# Zoul.net
KiCad netlist of a schematic drawn in Altium Designer
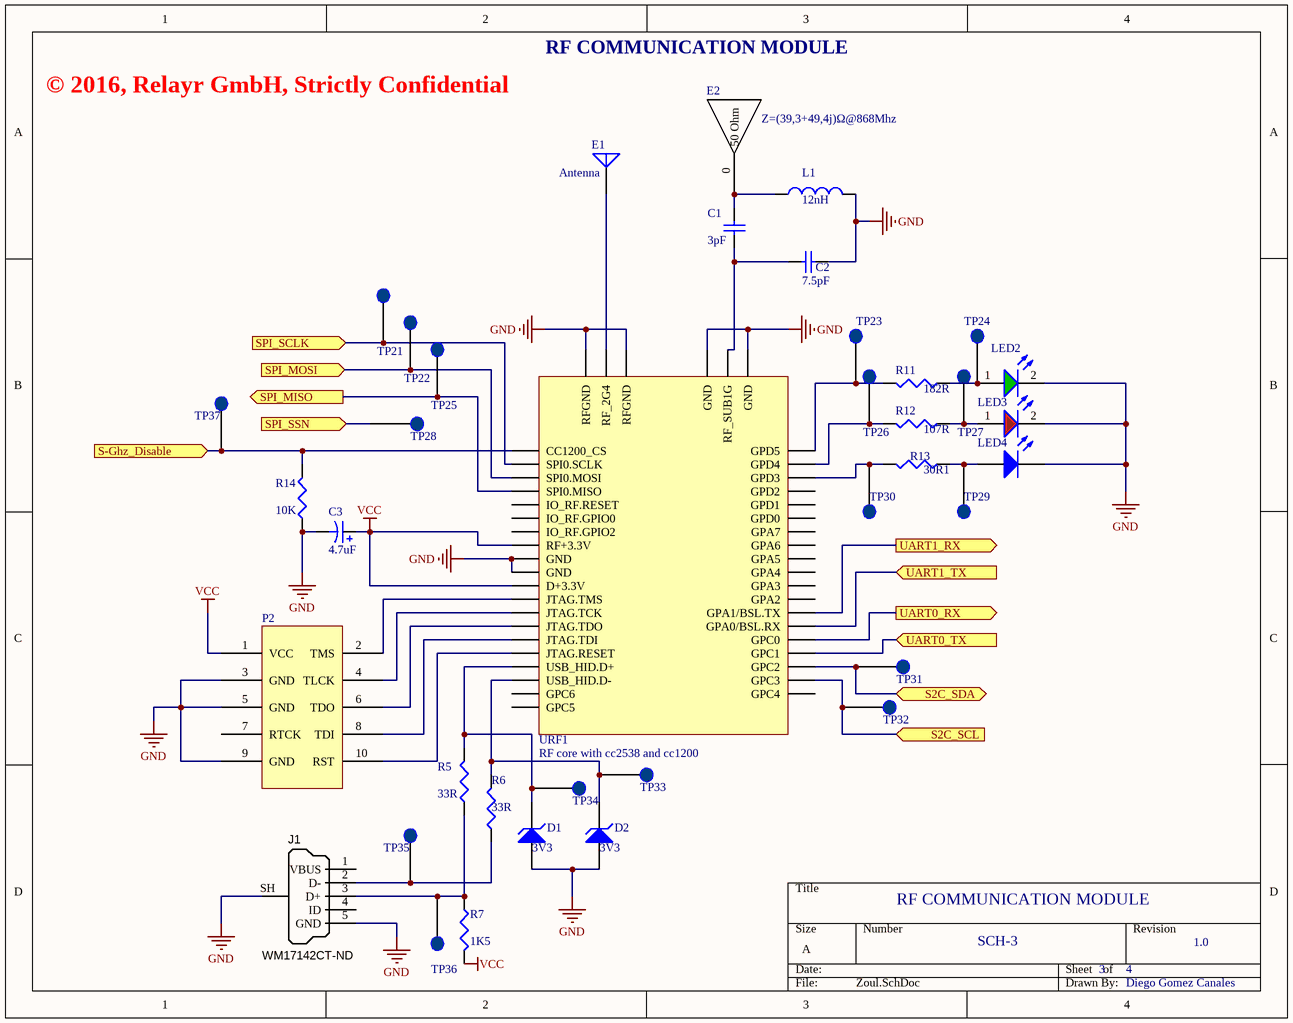
[diagram p0: Zoul.SchDoc]

(export (version "E")
  (design (tool "Eeschema 10.0.6"))
  (components
    (comp (ref "C1")
      (value "3pF")
      (footprint "6-0805_N")
      (description "Capacitor")
      (fields (field (name "Comment") "Cap") (field (name "PUBLISHER") "Altium Limited"))
      (libsource (lib "Miscellaneous Devices") (part "Cap"))
    )
    (comp (ref "C2")
      (value "7.5pF")
      (footprint "6-0805_N")
      (description "Capacitor")
      (fields (field (name "Comment") "Cap") (field (name "PUBLISHER") "Altium Limited"))
      (libsource (lib "Miscellaneous Devices") (part "Cap"))
    )
    (comp (ref "C3")
      (value "4.7uF")
      (footprint "C0805")
      (description "Polarized Capacitor (Surface Mount)")
      (fields (field (name "Comment") "Cap Pol3") (field (name "PUBLISHER") "Altium Limited"))
      (libsource (lib "Miscellaneous Devices") (part "Cap Pol3"))
    )
    (comp (ref "D1")
      (value "3V3")
      (footprint "425")
      (description "Zener Diode")
      (fields (field (name "PUBLISHER") "Altium Limited"))
      (libsource (lib "Miscellaneous Devices") (part "D Zener"))
    )
    (comp (ref "D2")
      (value "3V3")
      (footprint "425")
      (description "Zener Diode")
      (fields (field (name "PUBLISHER") "Altium Limited"))
      (libsource (lib "Miscellaneous Devices") (part "D Zener"))
    )
    (comp (ref "E1")
      (value "Antenna")
      (footprint "INDC3216")
      (description "Generic Antenna")
      (fields (field (name "PUBLISHER") "Altium Limited"))
      (libsource (lib "Miscellaneous Devices") (part "Antenna"))
    )
    (comp (ref "E2")
      (value "Component_1")
      (footprint "DNO24")
      (description "Antenna SubGhz PCB")
      (libsource (lib "SubGhz AntPCB") (part "Component_1"))
    )
    (comp (ref "J1")
      (value "USB Micro Type B")
      (footprint "USB_Micro-B_Molex_SMD")
      (description "Connector SMD USB Micro Type B middle mount")
      (fields (field (name "SUPPLIER PART NUMBER 1") "WM17142CT-ND"))
      (libsource (lib "Pasive_components") (part "USB_Micro_TypeB_1"))
    )
    (comp (ref "L1")
      (value "12nH")
      (footprint "6-0805_N")
      (description "Inductor")
      (fields (field (name "PUBLISHER") "Altium Limited"))
      (libsource (lib "Miscellaneous Devices") (part "Inductor"))
    )
    (comp (ref "LED2")
      (value "150080GS75000")
      (footprint "6-0805_N")
      (description "SMD mono-color Chip LED, WL-SMCW, Green")
      (fields
        (field (name "MANUFACTURER") "W黵th Elektronik eiSos GmbH")
        (field (name "CREATED BY") "Christin Otto")
      )
      (libsource (lib "SMD_LEDs") (part "WL-SMCW 0805  150080GS75000"))
    )
    (comp (ref "LED3")
      (value "150080RS75000")
      (footprint "6-0805_N")
      (description "SMD mono-color Chip LED, WL-SMCW, Red")
      (fields
        (field (name "MANUFACTURER") "W黵th Elektronik eiSos GmbH")
        (field (name "CREATED BY") "Christin Otto")
      )
      (libsource (lib "SMD_LEDs") (part "WL-SMCW 0805  150080RS75000"))
    )
    (comp (ref "LED4")
      (value "5988191107F")
      (footprint "6-0805_N")
      (description "Blue 473nm LED Indication - Discrete 3.2V 0805 (2012 Metric)")
      (fields (field (name "PUBLISHER") "Altium Limited"))
      (libsource (lib "Miscellaneous Devices") (part "LED0"))
    )
    (comp (ref "P2")
      (value "FTSH-105-01-L-DV-K")
      (footprint "JTAG")
      (libsource (lib "jtagConnector") (part "Component_1"))
    )
    (comp (ref "R5")
      (value "33R")
      (footprint "6-0805_N")
      (description "Resistor")
      (fields (field (name "Comment") "Res3") (field (name "PUBLISHER") "Altium Limited"))
      (libsource (lib "Miscellaneous Devices") (part "Res3"))
    )
    (comp (ref "R6")
      (value "33R")
      (footprint "6-0805_N")
      (description "Resistor")
      (fields (field (name "Comment") "Res3") (field (name "PUBLISHER") "Altium Limited"))
      (libsource (lib "Miscellaneous Devices") (part "Res3"))
    )
    (comp (ref "R7")
      (value "1K5")
      (footprint "6-0805_N")
      (description "Resistor")
      (fields (field (name "Comment") "Res3") (field (name "PUBLISHER") "Altium Limited"))
      (libsource (lib "Miscellaneous Devices") (part "Res3"))
    )
    (comp (ref "R11")
      (value "182R")
      (footprint "6-0805_N")
      (description "Resistor")
      (fields (field (name "Comment") "Res3") (field (name "PUBLISHER") "Altium Limited"))
      (libsource (lib "Miscellaneous Devices") (part "Res3"))
    )
    (comp (ref "R12")
      (value "107R")
      (footprint "6-0805_N")
      (description "Resistor")
      (fields (field (name "Comment") "Res3") (field (name "PUBLISHER") "Altium Limited"))
      (libsource (lib "Miscellaneous Devices") (part "Res3"))
    )
    (comp (ref "R13")
      (value "30R1")
      (footprint "6-0805_N")
      (description "Resistor")
      (fields (field (name "Comment") "Res3") (field (name "PUBLISHER") "Altium Limited"))
      (libsource (lib "Miscellaneous Devices") (part "Res3"))
    )
    (comp (ref "R14")
      (value "10K")
      (footprint "6-0805_N")
      (description "Resistor")
      (fields (field (name "Comment") "Res3") (field (name "PUBLISHER") "Altium Limited"))
      (libsource (lib "Miscellaneous Devices") (part "Res3"))
    )
    (comp (ref "TP21")
      (value "TEST_POINT")
      (footprint "TP")
      (description "Point of test to manufacturing")
      (libsource (lib "Pasive_components") (part "TEST_POINT"))
    )
    (comp (ref "TP22")
      (value "TEST_POINT")
      (footprint "TP")
      (description "Point of test to manufacturing")
      (libsource (lib "Pasive_components") (part "TEST_POINT"))
    )
    (comp (ref "TP23")
      (value "TEST_POINT")
      (footprint "TP")
      (description "Point of test to manufacturing")
      (libsource (lib "Pasive_components") (part "TEST_POINT"))
    )
    (comp (ref "TP24")
      (value "TEST_POINT")
      (footprint "TP")
      (description "Point of test to manufacturing")
      (libsource (lib "Pasive_components") (part "TEST_POINT"))
    )
    (comp (ref "TP25")
      (value "TEST_POINT")
      (footprint "TP")
      (description "Point of test to manufacturing")
      (libsource (lib "Pasive_components") (part "TEST_POINT"))
    )
    (comp (ref "TP26")
      (value "TEST_POINT")
      (footprint "TP")
      (description "Point of test to manufacturing")
      (libsource (lib "Pasive_components") (part "TEST_POINT"))
    )
    (comp (ref "TP27")
      (value "TEST_POINT")
      (footprint "TP")
      (description "Point of test to manufacturing")
      (libsource (lib "Pasive_components") (part "TEST_POINT"))
    )
    (comp (ref "TP28")
      (value "TEST_POINT")
      (footprint "TP")
      (description "Point of test to manufacturing")
      (libsource (lib "Pasive_components") (part "TEST_POINT"))
    )
    (comp (ref "TP29")
      (value "TEST_POINT")
      (footprint "TP")
      (description "Point of test to manufacturing")
      (libsource (lib "Pasive_components") (part "TEST_POINT"))
    )
    (comp (ref "TP30")
      (value "TEST_POINT")
      (footprint "TP")
      (description "Point of test to manufacturing")
      (libsource (lib "Pasive_components") (part "TEST_POINT"))
    )
    (comp (ref "TP31")
      (value "TEST_POINT")
      (footprint "TP")
      (description "Point of test to manufacturing")
      (libsource (lib "Pasive_components") (part "TEST_POINT"))
    )
    (comp (ref "TP32")
      (value "TEST_POINT")
      (footprint "TP")
      (description "Point of test to manufacturing")
      (libsource (lib "Pasive_components") (part "TEST_POINT"))
    )
    (comp (ref "TP33")
      (value "TEST_POINT")
      (footprint "TP")
      (description "Point of test to manufacturing")
      (libsource (lib "Pasive_components") (part "TEST_POINT"))
    )
    (comp (ref "TP34")
      (value "TEST_POINT")
      (footprint "TP")
      (description "Point of test to manufacturing")
      (libsource (lib "Pasive_components") (part "TEST_POINT"))
    )
    (comp (ref "TP35")
      (value "TEST_POINT")
      (footprint "TP")
      (description "Point of test to manufacturing")
      (libsource (lib "Pasive_components") (part "TEST_POINT"))
    )
    (comp (ref "TP36")
      (value "TEST_POINT")
      (footprint "TP")
      (description "Point of test to manufacturing")
      (libsource (lib "Pasive_components") (part "TEST_POINT"))
    )
    (comp (ref "TP37")
      (value "TEST_POINT")
      (footprint "TP")
      (description "Point of test to manufacturing")
      (libsource (lib "Pasive_components") (part "TEST_POINT"))
    )
    (comp (ref "URF1")
      (value "RF core with cc2538 and cc1200")
      (footprint "ZOUL")
      (libsource (lib "Zoul_RevA") (part "ZOUL"))
    )
  )
  (nets
    (net (code "1") (name "/S-Ghz_Disable") (class "Default")
      (node (ref "R14") (pin "2") (pinfunction "2_2") (pintype "passive"))
      (node (ref "TP37") (pin "1") (pintype "passive"))
      (node (ref "URF1") (pin "1") (pinfunction "CC1200_CS_1") (pintype "passive"))
    )
    (net (code "2") (name "/S2C_SCL") (class "Default")
      (node (ref "TP32") (pin "1") (pintype "passive"))
      (node (ref "URF1") (pin "22") (pinfunction "GPC3_22") (pintype "passive"))
    )
    (net (code "3") (name "/S2C_SDA") (class "Default")
      (node (ref "TP31") (pin "1") (pintype "passive"))
      (node (ref "URF1") (pin "23") (pinfunction "GPC2_23") (pintype "passive"))
    )
    (net (code "4") (name "/SPI_MISO") (class "Default")
      (node (ref "TP25") (pin "1") (pintype "passive"))
      (node (ref "URF1") (pin "4") (pinfunction "SPI0.MISO_4") (pintype "passive"))
    )
    (net (code "5") (name "/SPI_MOSI") (class "Default")
      (node (ref "TP22") (pin "1") (pintype "passive"))
      (node (ref "URF1") (pin "3") (pinfunction "SPI0.MOSI_3") (pintype "passive"))
    )
    (net (code "6") (name "/SPI_SCLK") (class "Default")
      (node (ref "TP21") (pin "1") (pintype "passive"))
      (node (ref "URF1") (pin "2") (pinfunction "SPI0.SCLK_2") (pintype "passive"))
    )
    (net (code "7") (name "/SPI_SSN") (class "Default") (node (ref "TP28") (pin "1") (pintype "passive")))
    (net (code "8") (name "/UART0_RX") (class "Default")
      (node (ref "URF1") (pin "25") (pinfunction "GPC0_25") (pintype "passive"))
    )
    (net (code "9") (name "/UART0_TX") (class "Default")
      (node (ref "URF1") (pin "24") (pinfunction "GPC1_24") (pintype "passive"))
    )
    (net (code "10") (name "/UART1_RX") (class "Default")
      (node (ref "URF1") (pin "27") (pinfunction "GPA1/BSL.TX_27") (pintype "passive"))
    )
    (net (code "11") (name "/UART1_TX") (class "Default")
      (node (ref "URF1") (pin "26") (pinfunction "GPA0/BSL.RX_26") (pintype "passive"))
    )
    (net (code "12") (name "GND") (class "Default")
      (node (ref "C2") (pin "1") (pinfunction "1_1") (pintype "passive"))
      (node (ref "C3") (pin "2") (pinfunction "2_2") (pintype "passive"))
      (node (ref "D1") (pin "1") (pinfunction "A_1") (pintype "passive"))
      (node (ref "D2") (pin "1") (pinfunction "A_1") (pintype "passive"))
      (node (ref "J1") (pin "5") (pinfunction "GND_5") (pintype "passive"))
      (node (ref "J1") (pin "SH") (pinfunction "Shell_SH") (pintype "passive"))
      (node (ref "L1") (pin "2") (pinfunction "2_2") (pintype "passive"))
      (node (ref "LED2") (pin "2") (pinfunction "C_2") (pintype "passive"))
      (node (ref "LED3") (pin "2") (pinfunction "C_2") (pintype "passive"))
      (node (ref "LED4") (pin "2") (pinfunction "K_2") (pintype "passive"))
      (node (ref "P2") (pin "3") (pinfunction "GND_3") (pintype "passive"))
      (node (ref "P2") (pin "5") (pinfunction "GND_5") (pintype "passive"))
      (node (ref "P2") (pin "9") (pinfunction "GND_9") (pintype "passive"))
      (node (ref "R14") (pin "1") (pinfunction "1_1") (pintype "passive"))
      (node (ref "URF1") (pin "10") (pinfunction "GND_10") (pintype "passive"))
      (node (ref "URF1") (pin "40") (pinfunction "GND_40") (pintype "passive"))
      (node (ref "URF1") (pin "42") (pinfunction "GND_42") (pintype "passive"))
      (node (ref "URF1") (pin "43") (pinfunction "RFGND_43") (pintype "passive"))
      (node (ref "URF1") (pin "45") (pinfunction "RFGND_45") (pintype "passive"))
      (node (ref "URF1") (pin "9") (pinfunction "GND_9") (pintype "passive"))
    )
    (net (code "13") (name "Net-(D1-K)") (class "Default")
      (node (ref "D1") (pin "2") (pinfunction "K_2") (pintype "passive"))
      (node (ref "R5") (pin "2") (pinfunction "2_2") (pintype "passive"))
      (node (ref "TP34") (pin "1") (pintype "passive"))
      (node (ref "URF1") (pin "17") (pinfunction "USB_HID.D+_17") (pintype "passive"))
    )
    (net (code "14") (name "Net-(D2-K)") (class "Default")
      (node (ref "D2") (pin "2") (pinfunction "K_2") (pintype "passive"))
      (node (ref "R6") (pin "2") (pinfunction "2_2") (pintype "passive"))
      (node (ref "TP33") (pin "1") (pintype "passive"))
      (node (ref "URF1") (pin "18") (pinfunction "USB_HID.D-_18") (pintype "passive"))
    )
    (net (code "15") (name "Net-(E1-A)") (class "Default")
      (node (ref "E1") (pin "1") (pinfunction "A_1") (pintype "passive"))
      (node (ref "URF1") (pin "44") (pinfunction "RF_2G4_44") (pintype "passive"))
    )
    (net (code "16") (name "Net-(E2-50_Ohm)") (class "Default")
      (node (ref "C1") (pin "2") (pinfunction "2_2") (pintype "passive"))
      (node (ref "E2") (pin "0") (pinfunction "50_Ohm_0") (pintype "passive"))
      (node (ref "L1") (pin "1") (pinfunction "1_1") (pintype "passive"))
    )
    (net (code "17") (name "Net-(J1-D+)") (class "Default")
      (node (ref "J1") (pin "3") (pinfunction "D+_3") (pintype "passive"))
      (node (ref "R5") (pin "1") (pinfunction "1_1") (pintype "passive"))
      (node (ref "R7") (pin "1") (pinfunction "1_1") (pintype "passive"))
      (node (ref "TP36") (pin "1") (pintype "passive"))
    )
    (net (code "18") (name "Net-(J1-D-)") (class "Default")
      (node (ref "J1") (pin "2") (pinfunction "D-_2") (pintype "passive"))
      (node (ref "R6") (pin "1") (pinfunction "1_1") (pintype "passive"))
      (node (ref "TP35") (pin "1") (pintype "passive"))
    )
    (net (code "19") (name "Net-(LED2-A)") (class "Default")
      (node (ref "LED2") (pin "1") (pinfunction "A_1") (pintype "passive"))
      (node (ref "R11") (pin "1") (pinfunction "1_1") (pintype "passive"))
      (node (ref "TP24") (pin "1") (pintype "passive"))
    )
    (net (code "20") (name "Net-(LED3-A)") (class "Default")
      (node (ref "LED3") (pin "1") (pinfunction "A_1") (pintype "passive"))
      (node (ref "R12") (pin "1") (pinfunction "1_1") (pintype "passive"))
      (node (ref "TP27") (pin "1") (pintype "passive"))
    )
    (net (code "21") (name "Net-(LED4-A)") (class "Default")
      (node (ref "LED4") (pin "1") (pinfunction "A_1") (pintype "passive"))
      (node (ref "R13") (pin "1") (pinfunction "1_1") (pintype "passive"))
      (node (ref "TP29") (pin "1") (pintype "passive"))
    )
    (net (code "22") (name "Net-(P2-RST)") (class "Default")
      (node (ref "P2") (pin "10") (pinfunction "RST_10") (pintype "passive"))
      (node (ref "URF1") (pin "16") (pinfunction "JTAG.RESET_16") (pintype "passive"))
    )
    (net (code "23") (name "Net-(P2-TDI)") (class "Default")
      (node (ref "P2") (pin "8") (pinfunction "TDI_8") (pintype "passive"))
      (node (ref "URF1") (pin "15") (pinfunction "JTAG.TDI_15") (pintype "passive"))
    )
    (net (code "24") (name "Net-(P2-TDO)") (class "Default")
      (node (ref "P2") (pin "6") (pinfunction "TDO_6") (pintype "passive"))
      (node (ref "URF1") (pin "14") (pinfunction "JTAG.TDO_14") (pintype "passive"))
    )
    (net (code "25") (name "Net-(P2-TLCK)") (class "Default")
      (node (ref "P2") (pin "4") (pinfunction "TLCK_4") (pintype "passive"))
      (node (ref "URF1") (pin "13") (pinfunction "JTAG.TCK_13") (pintype "passive"))
    )
    (net (code "26") (name "Net-(P2-TMS)") (class "Default")
      (node (ref "P2") (pin "2") (pinfunction "TMS_2") (pintype "passive"))
      (node (ref "URF1") (pin "12") (pinfunction "JTAG.TMS_12") (pintype "passive"))
    )
    (net (code "27") (name "Net-(URF1-GPD3)") (class "Default")
      (node (ref "R13") (pin "2") (pinfunction "2_2") (pintype "passive"))
      (node (ref "TP30") (pin "1") (pintype "passive"))
      (node (ref "URF1") (pin "37") (pinfunction "GPD3_37") (pintype "passive"))
    )
    (net (code "28") (name "Net-(URF1-GPD4)") (class "Default")
      (node (ref "R12") (pin "2") (pinfunction "2_2") (pintype "passive"))
      (node (ref "TP26") (pin "1") (pintype "passive"))
      (node (ref "URF1") (pin "38") (pinfunction "GPD4_38") (pintype "passive"))
    )
    (net (code "29") (name "Net-(URF1-GPD5)") (class "Default")
      (node (ref "R11") (pin "2") (pinfunction "2_2") (pintype "passive"))
      (node (ref "TP23") (pin "1") (pintype "passive"))
      (node (ref "URF1") (pin "39") (pinfunction "GPD5_39") (pintype "passive"))
    )
    (net (code "30") (name "Net-(URF1-RF_SUB1G)") (class "Default")
      (node (ref "C1") (pin "1") (pinfunction "1_1") (pintype "passive"))
      (node (ref "C2") (pin "2") (pinfunction "2_2") (pintype "passive"))
      (node (ref "URF1") (pin "41") (pinfunction "RF_SUB1G_41") (pintype "passive"))
    )
    (net (code "31") (name "VCC") (class "Default")
      (node (ref "C3") (pin "1") (pinfunction "1_1") (pintype "passive"))
      (node (ref "P2") (pin "1") (pinfunction "VCC_1") (pintype "passive"))
      (node (ref "R7") (pin "2") (pinfunction "2_2") (pintype "passive"))
      (node (ref "URF1") (pin "11") (pinfunction "D+3.3V_11") (pintype "passive"))
      (node (ref "URF1") (pin "8") (pinfunction "RF+3.3V_8") (pintype "passive"))
    )
    (net (code "32") (name "unconnected-(J1-ID-Pad4)") (class "Default")
      (node (ref "J1") (pin "4") (pinfunction "ID_4") (pintype "passive"))
    )
    (net (code "33") (name "unconnected-(J1-VBUS-Pad1)") (class "Default")
      (node (ref "J1") (pin "1") (pinfunction "VBUS_1") (pintype "passive"))
    )
    (net (code "34") (name "unconnected-(P2-RTCK-Pad7)") (class "Default")
      (node (ref "P2") (pin "7") (pinfunction "RTCK_7") (pintype "passive"))
    )
    (net (code "35") (name "unconnected-(URF1-GPA2-Pad28)") (class "Default")
      (node (ref "URF1") (pin "28") (pinfunction "GPA2_28") (pintype "passive"))
    )
    (net (code "36") (name "unconnected-(URF1-GPA3-Pad29)") (class "Default")
      (node (ref "URF1") (pin "29") (pinfunction "GPA3_29") (pintype "passive"))
    )
    (net (code "37") (name "unconnected-(URF1-GPA4-Pad30)") (class "Default")
      (node (ref "URF1") (pin "30") (pinfunction "GPA4_30") (pintype "passive"))
    )
    (net (code "38") (name "unconnected-(URF1-GPA5-Pad31)") (class "Default")
      (node (ref "URF1") (pin "31") (pinfunction "GPA5_31") (pintype "passive"))
    )
    (net (code "39") (name "unconnected-(URF1-GPA6-Pad32)") (class "Default")
      (node (ref "URF1") (pin "32") (pinfunction "GPA6_32") (pintype "passive"))
    )
    (net (code "40") (name "unconnected-(URF1-GPA7-Pad33)") (class "Default")
      (node (ref "URF1") (pin "33") (pinfunction "GPA7_33") (pintype "passive"))
    )
    (net (code "41") (name "unconnected-(URF1-GPC4-Pad21)") (class "Default")
      (node (ref "URF1") (pin "21") (pinfunction "GPC4_21") (pintype "passive"))
    )
    (net (code "42") (name "unconnected-(URF1-GPC5-Pad20)") (class "Default")
      (node (ref "URF1") (pin "20") (pinfunction "GPC5_20") (pintype "passive"))
    )
    (net (code "43") (name "unconnected-(URF1-GPC6-Pad19)") (class "Default")
      (node (ref "URF1") (pin "19") (pinfunction "GPC6_19") (pintype "passive"))
    )
    (net (code "44") (name "unconnected-(URF1-GPD0-Pad34)") (class "Default")
      (node (ref "URF1") (pin "34") (pinfunction "GPD0_34") (pintype "passive"))
    )
    (net (code "45") (name "unconnected-(URF1-GPD1-Pad35)") (class "Default")
      (node (ref "URF1") (pin "35") (pinfunction "GPD1_35") (pintype "passive"))
    )
    (net (code "46") (name "unconnected-(URF1-GPD2-Pad36)") (class "Default")
      (node (ref "URF1") (pin "36") (pinfunction "GPD2_36") (pintype "passive"))
    )
    (net (code "47") (name "unconnected-(URF1-IO_RF.GPIO0-Pad6)") (class "Default")
      (node (ref "URF1") (pin "6") (pinfunction "IO_RF.GPIO0_6") (pintype "passive"))
    )
    (net (code "48") (name "unconnected-(URF1-IO_RF.GPIO2-Pad7)") (class "Default")
      (node (ref "URF1") (pin "7") (pinfunction "IO_RF.GPIO2_7") (pintype "passive"))
    )
    (net (code "49") (name "unconnected-(URF1-IO_RF.RESET-Pad5)") (class "Default")
      (node (ref "URF1") (pin "5") (pinfunction "IO_RF.RESET_5") (pintype "passive"))
    )
  )
)
